# fotoresistenza_v1_rev0.net
KiCad netlist of a schematic drawn in EAGLE
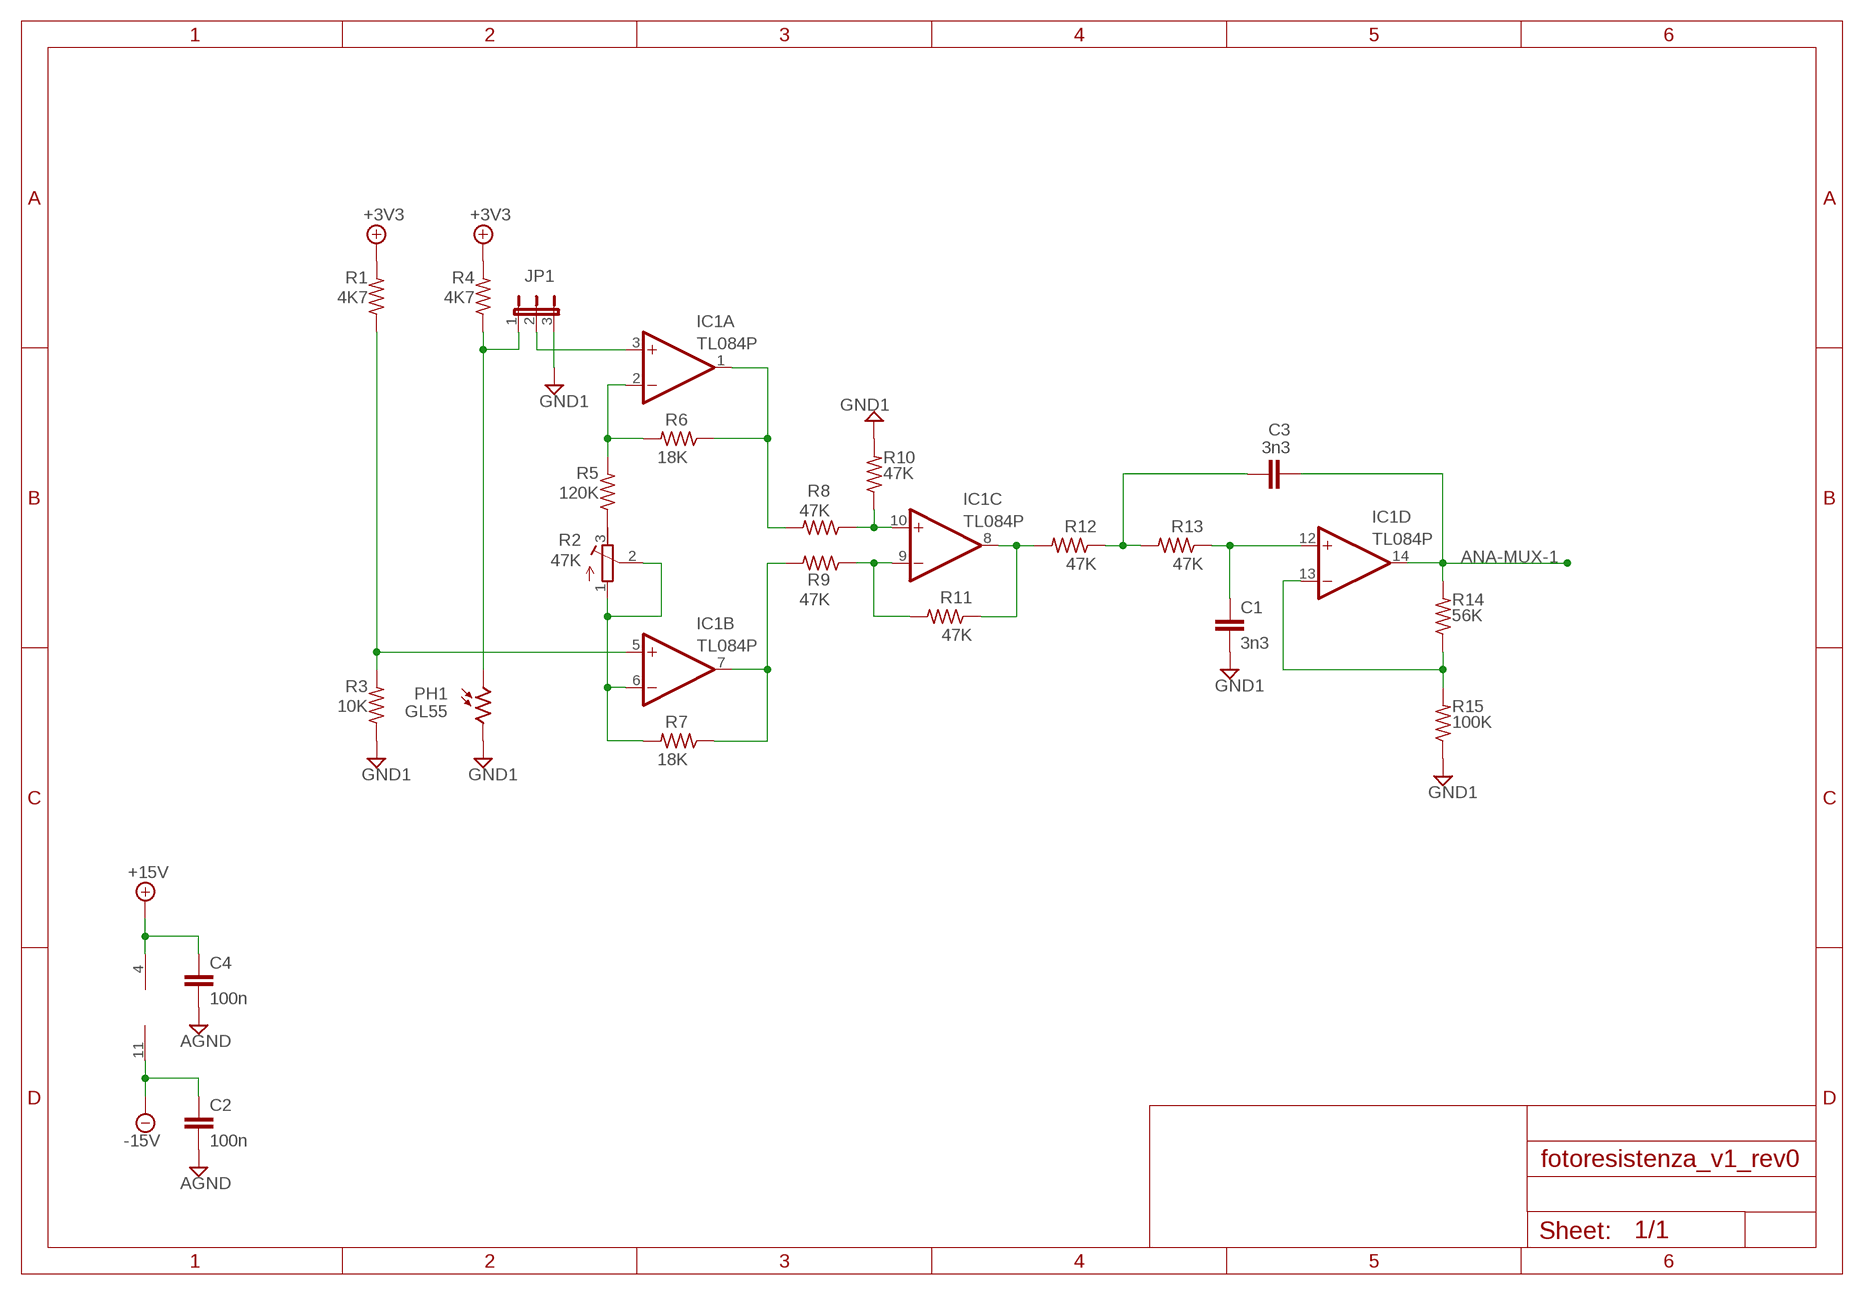
[diagram p0: schematic, sheet 1]

(export (version "E")
  (design (tool "Eeschema 10.0.6"))
  (components
    (comp (ref "C1")
      (value "3n3")
      (footprint "eagle-import:C025-025X050")
      (libsource (lib "eagle-import") (part "C-EU025-025X050"))
    )
    (comp (ref "C2")
      (value "100n")
      (footprint "eagle-import:C025-025X050")
      (libsource (lib "eagle-import") (part "C-EU025-025X050"))
    )
    (comp (ref "C3")
      (value "3n3")
      (footprint "eagle-import:C025-025X050")
      (libsource (lib "eagle-import") (part "C-EU025-025X050"))
    )
    (comp (ref "C4")
      (value "100n")
      (footprint "eagle-import:C025-025X050")
      (libsource (lib "eagle-import") (part "C-EU025-025X050"))
    )
    (comp (ref "IC1")
      (value "TL084P")
      (footprint "eagle-import:DIL14")
      (libsource (lib "eagle-import") (part "TL084P"))
    )
    (comp (ref "JP1")
      (value "JP2E")
      (footprint "eagle-import:JP2")
      (libsource (lib "eagle-import") (part "JP2E"))
    )
    (comp (ref "PH1")
      (value "GL55")
      (footprint "eagle-import:TO-8_B10")
      (fields (field (name "TYPE") "GL55"))
      (libsource (lib "eagle-import") (part "?1060B_23"))
    )
    (comp (ref "R1")
      (value "4K7")
      (footprint "eagle-import:0204_7")
      (libsource (lib "eagle-import") (part "R-US_0204/7"))
    )
    (comp (ref "R2")
      (value "47K")
      (footprint "eagle-import:RTRIM64W")
      (libsource (lib "eagle-import") (part "R-TRIMM64W"))
    )
    (comp (ref "R3")
      (value "10K")
      (footprint "eagle-import:0204_7")
      (libsource (lib "eagle-import") (part "R-US_0204/7"))
    )
    (comp (ref "R4")
      (value "4K7")
      (footprint "eagle-import:0204_7")
      (libsource (lib "eagle-import") (part "R-US_0204/7"))
    )
    (comp (ref "R5")
      (value "120K")
      (footprint "eagle-import:0204_7")
      (libsource (lib "eagle-import") (part "R-US_0204/7"))
    )
    (comp (ref "R6")
      (value "18K")
      (footprint "eagle-import:0204_7")
      (libsource (lib "eagle-import") (part "R-US_0204/7"))
    )
    (comp (ref "R7")
      (value "18K")
      (footprint "eagle-import:0204_7")
      (libsource (lib "eagle-import") (part "R-US_0204/7"))
    )
    (comp (ref "R8")
      (value "47K")
      (footprint "eagle-import:0204_7")
      (libsource (lib "eagle-import") (part "R-US_0204/7"))
    )
    (comp (ref "R9")
      (value "47K")
      (footprint "eagle-import:0204_7")
      (libsource (lib "eagle-import") (part "R-US_0204/7"))
    )
    (comp (ref "R10")
      (value "47K")
      (footprint "eagle-import:0204_7")
      (libsource (lib "eagle-import") (part "R-US_0204/7"))
    )
    (comp (ref "R11")
      (value "47K")
      (footprint "eagle-import:0204_7")
      (libsource (lib "eagle-import") (part "R-US_0204/7"))
    )
    (comp (ref "R12")
      (value "47K")
      (footprint "eagle-import:0204_7")
      (libsource (lib "eagle-import") (part "R-US_0204/7"))
    )
    (comp (ref "R13")
      (value "47K")
      (footprint "eagle-import:0204_7")
      (libsource (lib "eagle-import") (part "R-US_0204/7"))
    )
    (comp (ref "R14")
      (value "56K")
      (footprint "eagle-import:0204_7")
      (libsource (lib "eagle-import") (part "R-US_0204/7"))
    )
    (comp (ref "R15")
      (value "100K")
      (footprint "eagle-import:0204_7")
      (libsource (lib "eagle-import") (part "R-US_0204/7"))
    )
  )
  (nets
    (net (code "1") (name "+3V3") (class "Default")
      (node (ref "R1") (pin "2") (pinfunction "2_2") (pintype "passive"))
      (node (ref "R4") (pin "2") (pinfunction "2_2") (pintype "passive"))
    )
    (net (code "2") (name "+15V") (class "Default")
      (node (ref "C4") (pin "1") (pinfunction "1_1") (pintype "passive"))
      (node (ref "IC1") (pin "4") (pinfunction "V+_4") (pintype "power_in"))
    )
    (net (code "3") (name "-15V") (class "Default")
      (node (ref "C2") (pin "1") (pinfunction "1_1") (pintype "passive"))
      (node (ref "IC1") (pin "11") (pinfunction "V-_11") (pintype "power_in"))
    )
    (net (code "4") (name "/ANA-MUX-1") (class "Default")
      (node (ref "C3") (pin "2") (pinfunction "2_2") (pintype "passive"))
      (node (ref "IC1") (pin "14") (pinfunction "OUT_14") (pintype "output"))
      (node (ref "R14") (pin "2") (pinfunction "2_2") (pintype "passive"))
    )
    (net (code "5") (name "AGND") (class "Default")
      (node (ref "C2") (pin "2") (pinfunction "2_2") (pintype "passive"))
      (node (ref "C4") (pin "2") (pinfunction "2_2") (pintype "passive"))
    )
    (net (code "6") (name "GND1") (class "Default")
      (node (ref "C1") (pin "2") (pinfunction "2_2") (pintype "passive"))
      (node (ref "JP1") (pin "3") (pinfunction "3_3") (pintype "passive"))
      (node (ref "PH1") (pin "2") (pinfunction "2_2") (pintype "passive"))
      (node (ref "R10") (pin "2") (pinfunction "2_2") (pintype "passive"))
      (node (ref "R15") (pin "1") (pinfunction "1_1") (pintype "passive"))
      (node (ref "R3") (pin "1") (pinfunction "1_1") (pintype "passive"))
    )
    (net (code "7") (name "Net-(C3-Pad1)") (class "Default")
      (node (ref "C3") (pin "1") (pinfunction "1_1") (pintype "passive"))
      (node (ref "R12") (pin "1") (pinfunction "1_1") (pintype "passive"))
      (node (ref "R13") (pin "2") (pinfunction "2_2") (pintype "passive"))
    )
    (net (code "8") (name "Net-(IC1A-+IN)") (class "Default")
      (node (ref "IC1") (pin "3") (pinfunction "+IN_3") (pintype "input"))
      (node (ref "JP1") (pin "2") (pinfunction "2_2") (pintype "passive"))
    )
    (net (code "9") (name "Net-(IC1A--IN)") (class "Default")
      (node (ref "IC1") (pin "2") (pinfunction "-IN_2") (pintype "input"))
      (node (ref "R5") (pin "2") (pinfunction "2_2") (pintype "passive"))
      (node (ref "R6") (pin "2") (pinfunction "2_2") (pintype "passive"))
    )
    (net (code "10") (name "Net-(IC1A-OUT)") (class "Default")
      (node (ref "IC1") (pin "1") (pinfunction "OUT_1") (pintype "output"))
      (node (ref "R6") (pin "1") (pinfunction "1_1") (pintype "passive"))
      (node (ref "R8") (pin "2") (pinfunction "2_2") (pintype "passive"))
    )
    (net (code "11") (name "Net-(IC1B-+IN)") (class "Default")
      (node (ref "IC1") (pin "5") (pinfunction "+IN_5") (pintype "input"))
      (node (ref "R1") (pin "1") (pinfunction "1_1") (pintype "passive"))
      (node (ref "R3") (pin "2") (pinfunction "2_2") (pintype "passive"))
    )
    (net (code "12") (name "Net-(IC1B--IN)") (class "Default")
      (node (ref "IC1") (pin "6") (pinfunction "-IN_6") (pintype "input"))
      (node (ref "R2") (pin "1") (pinfunction "E_1") (pintype "passive"))
      (node (ref "R2") (pin "2") (pinfunction "S_2") (pintype "passive"))
      (node (ref "R7") (pin "2") (pinfunction "2_2") (pintype "passive"))
    )
    (net (code "13") (name "Net-(IC1B-OUT)") (class "Default")
      (node (ref "IC1") (pin "7") (pinfunction "OUT_7") (pintype "output"))
      (node (ref "R7") (pin "1") (pinfunction "1_1") (pintype "passive"))
      (node (ref "R9") (pin "2") (pinfunction "2_2") (pintype "passive"))
    )
    (net (code "14") (name "Net-(IC1C-+IN)") (class "Default")
      (node (ref "IC1") (pin "10") (pinfunction "+IN_10") (pintype "input"))
      (node (ref "R10") (pin "1") (pinfunction "1_1") (pintype "passive"))
      (node (ref "R8") (pin "1") (pinfunction "1_1") (pintype "passive"))
    )
    (net (code "15") (name "Net-(IC1C--IN)") (class "Default")
      (node (ref "IC1") (pin "9") (pinfunction "-IN_9") (pintype "input"))
      (node (ref "R11") (pin "2") (pinfunction "2_2") (pintype "passive"))
      (node (ref "R9") (pin "1") (pinfunction "1_1") (pintype "passive"))
    )
    (net (code "16") (name "Net-(IC1C-OUT)") (class "Default")
      (node (ref "IC1") (pin "8") (pinfunction "OUT_8") (pintype "output"))
      (node (ref "R11") (pin "1") (pinfunction "1_1") (pintype "passive"))
      (node (ref "R12") (pin "2") (pinfunction "2_2") (pintype "passive"))
    )
    (net (code "17") (name "Net-(IC1D-+IN)") (class "Default")
      (node (ref "C1") (pin "1") (pinfunction "1_1") (pintype "passive"))
      (node (ref "IC1") (pin "12") (pinfunction "+IN_12") (pintype "input"))
      (node (ref "R13") (pin "1") (pinfunction "1_1") (pintype "passive"))
    )
    (net (code "18") (name "Net-(IC1D--IN)") (class "Default")
      (node (ref "IC1") (pin "13") (pinfunction "-IN_13") (pintype "input"))
      (node (ref "R14") (pin "1") (pinfunction "1_1") (pintype "passive"))
      (node (ref "R15") (pin "2") (pinfunction "2_2") (pintype "passive"))
    )
    (net (code "19") (name "Net-(JP1-Pad1)") (class "Default")
      (node (ref "JP1") (pin "1") (pinfunction "1_1") (pintype "passive"))
      (node (ref "PH1") (pin "1") (pinfunction "1_1") (pintype "passive"))
      (node (ref "R4") (pin "1") (pinfunction "1_1") (pintype "passive"))
    )
    (net (code "20") (name "Net-(R2-A)") (class "Default")
      (node (ref "R2") (pin "3") (pinfunction "A_3") (pintype "passive"))
      (node (ref "R5") (pin "1") (pinfunction "1_1") (pintype "passive"))
    )
  )
)
